# Keyboard_Mouse_LED_Monitor.net
KiCad netlist of a schematic drawn in Altium Designer
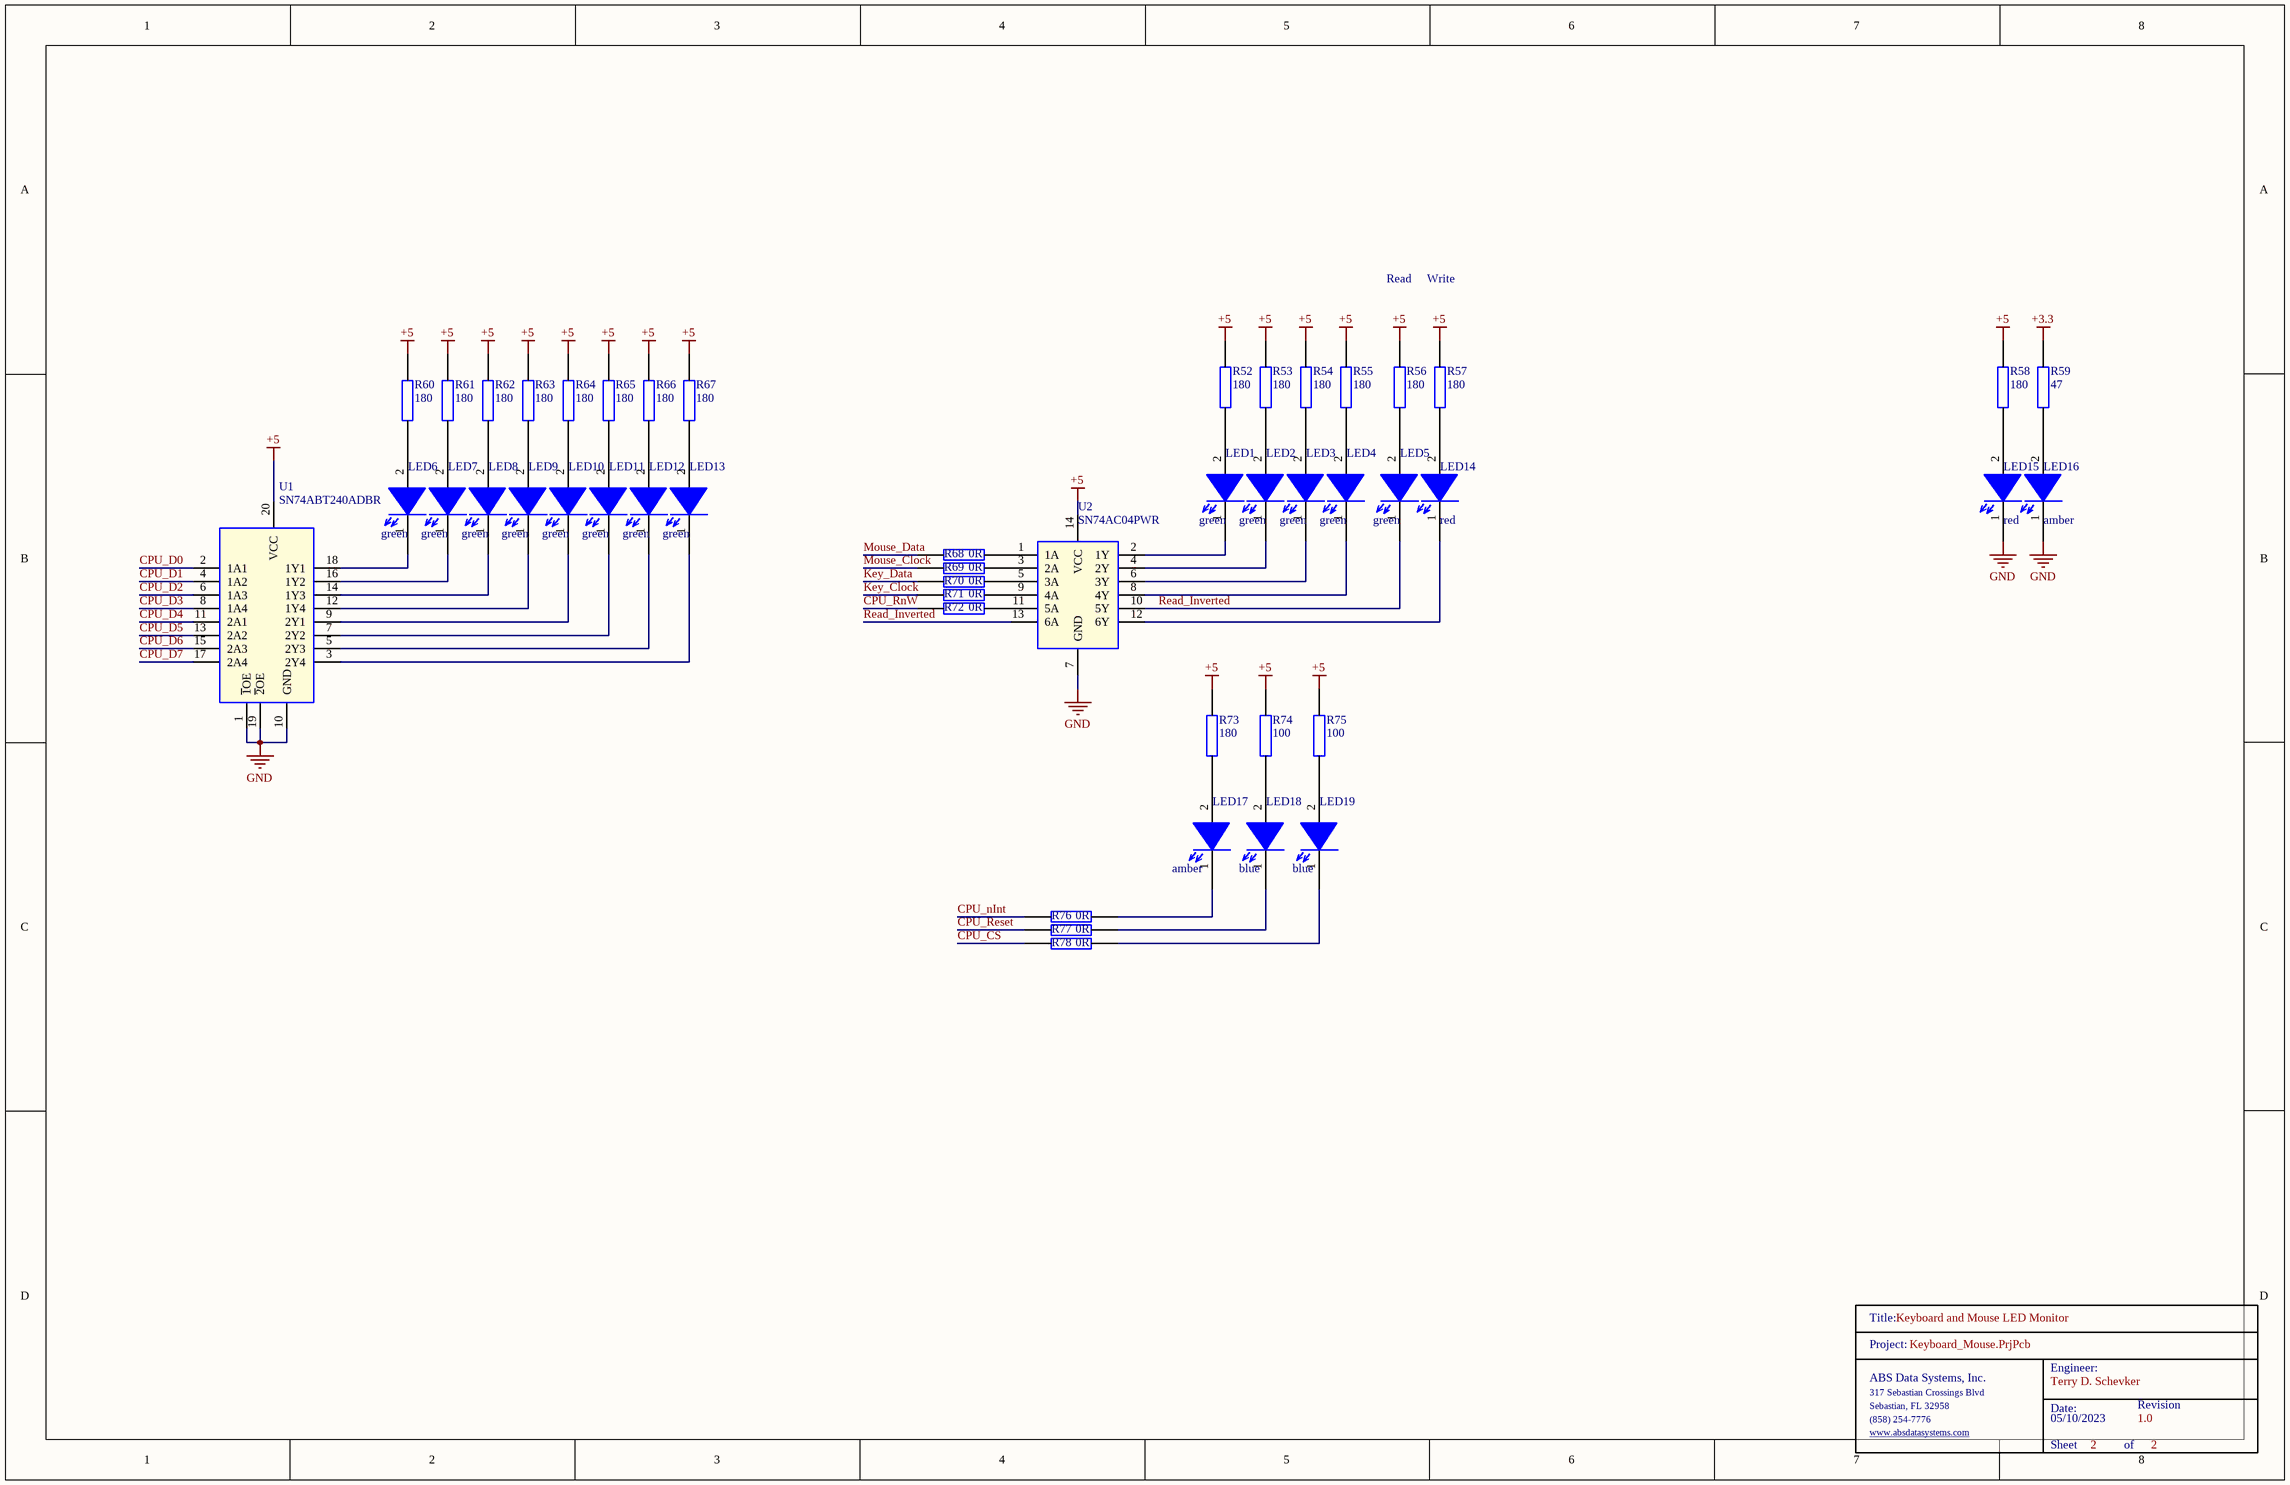
[diagram p0: Keyboard_Mouse_LED_Monitor.SchDoc]

(export (version "E")
  (design (tool "Eeschema 10.0.6"))
  (components
    (comp (ref "LED1")
      (value "green")
      (footprint "0603_Diode")
      (description "Wurth Elektronik 0603 green")
      (fields
        (field (name "MANUFACTURER") "Wurth Electronics")
        (field (name "MANUFACTURER PART NUMBER") "150060GS75000")
      )
      (libsource (lib "Misc") (part "150060GS75000"))
    )
    (comp (ref "LED2")
      (value "green")
      (footprint "0603_Diode")
      (description "Wurth Elektronik 0603 green")
      (fields
        (field (name "MANUFACTURER") "Wurth Electronics")
        (field (name "MANUFACTURER PART NUMBER") "150060GS75000")
      )
      (libsource (lib "Misc") (part "150060GS75000"))
    )
    (comp (ref "LED3")
      (value "green")
      (footprint "0603_Diode")
      (description "Wurth Elektronik 0603 green")
      (fields
        (field (name "MANUFACTURER") "Wurth Electronics")
        (field (name "MANUFACTURER PART NUMBER") "150060GS75000")
      )
      (libsource (lib "Misc") (part "150060GS75000"))
    )
    (comp (ref "LED4")
      (value "green")
      (footprint "0603_Diode")
      (description "Wurth Elektronik 0603 green")
      (fields
        (field (name "MANUFACTURER") "Wurth Electronics")
        (field (name "MANUFACTURER PART NUMBER") "150060GS75000")
      )
      (libsource (lib "Misc") (part "150060GS75000"))
    )
    (comp (ref "LED5")
      (value "green")
      (footprint "0603_Diode")
      (description "Wurth Elektronik 0603 green")
      (fields
        (field (name "MANUFACTURER") "Wurth Electronics")
        (field (name "MANUFACTURER PART NUMBER") "150060GS75000")
      )
      (libsource (lib "Misc") (part "150060GS75000"))
    )
    (comp (ref "LED6")
      (value "green")
      (footprint "0603_Diode")
      (description "Wurth Elektronik 0603 green")
      (fields
        (field (name "MANUFACTURER") "Wurth Electronics")
        (field (name "MANUFACTURER PART NUMBER") "150060GS75000")
      )
      (libsource (lib "Misc") (part "150060GS75000"))
    )
    (comp (ref "LED7")
      (value "green")
      (footprint "0603_Diode")
      (description "Wurth Elektronik 0603 green")
      (fields
        (field (name "MANUFACTURER") "Wurth Electronics")
        (field (name "MANUFACTURER PART NUMBER") "150060GS75000")
      )
      (libsource (lib "Misc") (part "150060GS75000"))
    )
    (comp (ref "LED8")
      (value "green")
      (footprint "0603_Diode")
      (description "Wurth Elektronik 0603 green")
      (fields
        (field (name "MANUFACTURER") "Wurth Electronics")
        (field (name "MANUFACTURER PART NUMBER") "150060GS75000")
      )
      (libsource (lib "Misc") (part "150060GS75000"))
    )
    (comp (ref "LED9")
      (value "green")
      (footprint "0603_Diode")
      (description "Wurth Elektronik 0603 green")
      (fields
        (field (name "MANUFACTURER") "Wurth Electronics")
        (field (name "MANUFACTURER PART NUMBER") "150060GS75000")
      )
      (libsource (lib "Misc") (part "150060GS75000"))
    )
    (comp (ref "LED10")
      (value "green")
      (footprint "0603_Diode")
      (description "Wurth Elektronik 0603 green")
      (fields
        (field (name "MANUFACTURER") "Wurth Electronics")
        (field (name "MANUFACTURER PART NUMBER") "150060GS75000")
      )
      (libsource (lib "Misc") (part "150060GS75000"))
    )
    (comp (ref "LED11")
      (value "green")
      (footprint "0603_Diode")
      (description "Wurth Elektronik 0603 green")
      (fields
        (field (name "MANUFACTURER") "Wurth Electronics")
        (field (name "MANUFACTURER PART NUMBER") "150060GS75000")
      )
      (libsource (lib "Misc") (part "150060GS75000"))
    )
    (comp (ref "LED12")
      (value "green")
      (footprint "0603_Diode")
      (description "Wurth Elektronik 0603 green")
      (fields
        (field (name "MANUFACTURER") "Wurth Electronics")
        (field (name "MANUFACTURER PART NUMBER") "150060GS75000")
      )
      (libsource (lib "Misc") (part "150060GS75000"))
    )
    (comp (ref "LED13")
      (value "green")
      (footprint "0603_Diode")
      (description "Wurth Elektronik 0603 green")
      (fields
        (field (name "MANUFACTURER") "Wurth Electronics")
        (field (name "MANUFACTURER PART NUMBER") "150060GS75000")
      )
      (libsource (lib "Misc") (part "150060GS75000"))
    )
    (comp (ref "LED14")
      (value "red")
      (footprint "0603_Diode")
      (description "Wurth Elektronik 0603 red")
      (fields
        (field (name "MANUFACTURER") "Wurth Electronics")
        (field (name "MANUFACTURER PART NUMBER") "150060GS75000")
      )
      (libsource (lib "Misc") (part "150060RS75000"))
    )
    (comp (ref "LED15")
      (value "red")
      (footprint "0603_Diode")
      (description "Wurth Elektronik 0603 red")
      (fields
        (field (name "MANUFACTURER") "Wurth Electronics")
        (field (name "MANUFACTURER PART NUMBER") "150060GS75000")
      )
      (libsource (lib "Misc") (part "150060RS75000"))
    )
    (comp (ref "LED16")
      (value "amber")
      (footprint "0603_Diode")
      (description "Wurth Elektronik 0603 amber")
      (fields
        (field (name "MANUFACTURER") "Wurth Electronics")
        (field (name "MANUFACTURER PART NUMBER") "150060GS75000")
      )
      (libsource (lib "Misc") (part "150060AS75000"))
    )
    (comp (ref "LED17")
      (value "amber")
      (footprint "0603_Diode")
      (description "Wurth Elektronik 0603 amber")
      (fields
        (field (name "MANUFACTURER") "Wurth Electronics")
        (field (name "MANUFACTURER PART NUMBER") "150060GS75000")
      )
      (libsource (lib "Misc") (part "150060AS75000"))
    )
    (comp (ref "LED18")
      (value "blue")
      (footprint "0603_Diode")
      (description "Wurth Elektronik 0603 blue")
      (fields
        (field (name "MANUFACTURER") "Wurth Electronics")
        (field (name "MANUFACTURER PART NUMBER") "150060GS75000")
      )
      (libsource (lib "Misc") (part "150060BS75000"))
    )
    (comp (ref "LED19")
      (value "blue")
      (footprint "0603_Diode")
      (description "Wurth Elektronik 0603 blue")
      (fields
        (field (name "MANUFACTURER") "Wurth Electronics")
        (field (name "MANUFACTURER PART NUMBER") "150060GS75000")
      )
      (libsource (lib "Misc") (part "150060BS75000"))
    )
    (comp (ref "R52")
      (value "180")
      (footprint "0603")
      (description "YAGEO 0603 180 ohm")
      (fields
        (field (name "MOUSER PART NUMBER") "603-RC0603JR-070RL")
        (field (name "MANUFACTURER_PART_NUMBER") "RC0603JR-070RL")
      )
      (libsource (lib "Resistors") (part "RC0603FR-13180RL"))
    )
    (comp (ref "R53")
      (value "180")
      (footprint "0603")
      (description "YAGEO 0603 180 ohm")
      (fields
        (field (name "MOUSER PART NUMBER") "603-RC0603JR-070RL")
        (field (name "MANUFACTURER_PART_NUMBER") "RC0603JR-070RL")
      )
      (libsource (lib "Resistors") (part "RC0603FR-13180RL"))
    )
    (comp (ref "R54")
      (value "180")
      (footprint "0603")
      (description "YAGEO 0603 180 ohm")
      (fields
        (field (name "MOUSER PART NUMBER") "603-RC0603JR-070RL")
        (field (name "MANUFACTURER_PART_NUMBER") "RC0603JR-070RL")
      )
      (libsource (lib "Resistors") (part "RC0603FR-13180RL"))
    )
    (comp (ref "R55")
      (value "180")
      (footprint "0603")
      (description "YAGEO 0603 180 ohm")
      (fields
        (field (name "MOUSER PART NUMBER") "603-RC0603JR-070RL")
        (field (name "MANUFACTURER_PART_NUMBER") "RC0603JR-070RL")
      )
      (libsource (lib "Resistors") (part "RC0603FR-13180RL"))
    )
    (comp (ref "R56")
      (value "180")
      (footprint "0603")
      (description "YAGEO 0603 180 ohm")
      (fields
        (field (name "MOUSER PART NUMBER") "603-RC0603JR-070RL")
        (field (name "MANUFACTURER_PART_NUMBER") "RC0603JR-070RL")
      )
      (libsource (lib "Resistors") (part "RC0603FR-13180RL"))
    )
    (comp (ref "R57")
      (value "180")
      (footprint "0603")
      (description "YAGEO 0603 180 ohm")
      (fields
        (field (name "MOUSER PART NUMBER") "603-RC0603JR-070RL")
        (field (name "MANUFACTURER_PART_NUMBER") "RC0603JR-070RL")
      )
      (libsource (lib "Resistors") (part "RC0603FR-13180RL"))
    )
    (comp (ref "R58")
      (value "180")
      (footprint "0603")
      (description "YAGEO 0603 180 ohm")
      (fields
        (field (name "MOUSER PART NUMBER") "603-RC0603JR-070RL")
        (field (name "MANUFACTURER_PART_NUMBER") "RC0603JR-070RL")
      )
      (libsource (lib "Resistors") (part "RC0603FR-13180RL"))
    )
    (comp (ref "R59")
      (value "47")
      (footprint "0603")
      (description "YAGEO 0603 47")
      (fields
        (field (name "MOUSER PART NUMBER") "603-RC0603JR-070RL")
        (field (name "MANUFACTURER_PART_NUMBER") "RC0603JR-070RL")
      )
      (libsource (lib "Resistors") (part "RC0603FR-0747KL"))
    )
    (comp (ref "R60")
      (value "180")
      (footprint "0603")
      (description "YAGEO 0603 180 ohm")
      (fields
        (field (name "MOUSER PART NUMBER") "603-RC0603JR-070RL")
        (field (name "MANUFACTURER_PART_NUMBER") "RC0603JR-070RL")
      )
      (libsource (lib "Resistors") (part "RC0603FR-13180RL"))
    )
    (comp (ref "R61")
      (value "180")
      (footprint "0603")
      (description "YAGEO 0603 180 ohm")
      (fields
        (field (name "MOUSER PART NUMBER") "603-RC0603JR-070RL")
        (field (name "MANUFACTURER_PART_NUMBER") "RC0603JR-070RL")
      )
      (libsource (lib "Resistors") (part "RC0603FR-13180RL"))
    )
    (comp (ref "R62")
      (value "180")
      (footprint "0603")
      (description "YAGEO 0603 180 ohm")
      (fields
        (field (name "MOUSER PART NUMBER") "603-RC0603JR-070RL")
        (field (name "MANUFACTURER_PART_NUMBER") "RC0603JR-070RL")
      )
      (libsource (lib "Resistors") (part "RC0603FR-13180RL"))
    )
    (comp (ref "R63")
      (value "180")
      (footprint "0603")
      (description "YAGEO 0603 180 ohm")
      (fields
        (field (name "MOUSER PART NUMBER") "603-RC0603JR-070RL")
        (field (name "MANUFACTURER_PART_NUMBER") "RC0603JR-070RL")
      )
      (libsource (lib "Resistors") (part "RC0603FR-13180RL"))
    )
    (comp (ref "R64")
      (value "180")
      (footprint "0603")
      (description "YAGEO 0603 180 ohm")
      (fields
        (field (name "MOUSER PART NUMBER") "603-RC0603JR-070RL")
        (field (name "MANUFACTURER_PART_NUMBER") "RC0603JR-070RL")
      )
      (libsource (lib "Resistors") (part "RC0603FR-13180RL"))
    )
    (comp (ref "R65")
      (value "180")
      (footprint "0603")
      (description "YAGEO 0603 180 ohm")
      (fields
        (field (name "MOUSER PART NUMBER") "603-RC0603JR-070RL")
        (field (name "MANUFACTURER_PART_NUMBER") "RC0603JR-070RL")
      )
      (libsource (lib "Resistors") (part "RC0603FR-13180RL"))
    )
    (comp (ref "R66")
      (value "180")
      (footprint "0603")
      (description "YAGEO 0603 180 ohm")
      (fields
        (field (name "MOUSER PART NUMBER") "603-RC0603JR-070RL")
        (field (name "MANUFACTURER_PART_NUMBER") "RC0603JR-070RL")
      )
      (libsource (lib "Resistors") (part "RC0603FR-13180RL"))
    )
    (comp (ref "R67")
      (value "180")
      (footprint "0603")
      (description "YAGEO 0603 180 ohm")
      (fields
        (field (name "MOUSER PART NUMBER") "603-RC0603JR-070RL")
        (field (name "MANUFACTURER_PART_NUMBER") "RC0603JR-070RL")
      )
      (libsource (lib "Resistors") (part "RC0603FR-13180RL"))
    )
    (comp (ref "R68")
      (value "0R")
      (footprint "0603")
      (description "YAGEO 0603 0 ohm")
      (fields
        (field (name "MOUSER PART NUMBER") "603-RC0603JR-070RL")
        (field (name "MANUFACTURER_PART_NUMBER") "RC0603JR-070RL")
      )
      (libsource (lib "Resistors") (part "RC0603JR-070RL"))
    )
    (comp (ref "R69")
      (value "0R")
      (footprint "0603")
      (description "YAGEO 0603 0 ohm")
      (fields
        (field (name "MOUSER PART NUMBER") "603-RC0603JR-070RL")
        (field (name "MANUFACTURER_PART_NUMBER") "RC0603JR-070RL")
      )
      (libsource (lib "Resistors") (part "RC0603JR-070RL"))
    )
    (comp (ref "R70")
      (value "0R")
      (footprint "0603")
      (description "YAGEO 0603 0 ohm")
      (fields
        (field (name "MOUSER PART NUMBER") "603-RC0603JR-070RL")
        (field (name "MANUFACTURER_PART_NUMBER") "RC0603JR-070RL")
      )
      (libsource (lib "Resistors") (part "RC0603JR-070RL"))
    )
    (comp (ref "R71")
      (value "0R")
      (footprint "0603")
      (description "YAGEO 0603 0 ohm")
      (fields
        (field (name "MOUSER PART NUMBER") "603-RC0603JR-070RL")
        (field (name "MANUFACTURER_PART_NUMBER") "RC0603JR-070RL")
      )
      (libsource (lib "Resistors") (part "RC0603JR-070RL"))
    )
    (comp (ref "R72")
      (value "0R")
      (footprint "0603")
      (description "YAGEO 0603 0 ohm")
      (fields
        (field (name "MOUSER PART NUMBER") "603-RC0603JR-070RL")
        (field (name "MANUFACTURER_PART_NUMBER") "RC0603JR-070RL")
      )
      (libsource (lib "Resistors") (part "RC0603JR-070RL"))
    )
    (comp (ref "R73")
      (value "180")
      (footprint "0603")
      (description "YAGEO 0603 180 ohm")
      (fields
        (field (name "MOUSER PART NUMBER") "603-RC0603JR-070RL")
        (field (name "MANUFACTURER_PART_NUMBER") "RC0603JR-070RL")
      )
      (libsource (lib "Resistors") (part "RC0603FR-13180RL"))
    )
    (comp (ref "R74")
      (value "100")
      (footprint "0603")
      (description "YAGEO 0603 100 ohm")
      (fields
        (field (name "MOUSER PART NUMBER") "603-RC0603JR-070RL")
        (field (name "MANUFACTURER_PART_NUMBER") "RC0603JR-070RL")
      )
      (libsource (lib "Resistors") (part "RC0603FR-10100RL"))
    )
    (comp (ref "R75")
      (value "100")
      (footprint "0603")
      (description "YAGEO 0603 100 ohm")
      (fields
        (field (name "MOUSER PART NUMBER") "603-RC0603JR-070RL")
        (field (name "MANUFACTURER_PART_NUMBER") "RC0603JR-070RL")
      )
      (libsource (lib "Resistors") (part "RC0603FR-10100RL"))
    )
    (comp (ref "R76")
      (value "0R")
      (footprint "0603")
      (description "YAGEO 0603 0 ohm")
      (fields
        (field (name "MOUSER PART NUMBER") "603-RC0603JR-070RL")
        (field (name "MANUFACTURER_PART_NUMBER") "RC0603JR-070RL")
      )
      (libsource (lib "Resistors") (part "RC0603JR-070RL"))
    )
    (comp (ref "R77")
      (value "0R")
      (footprint "0603")
      (description "YAGEO 0603 0 ohm")
      (fields
        (field (name "MOUSER PART NUMBER") "603-RC0603JR-070RL")
        (field (name "MANUFACTURER_PART_NUMBER") "RC0603JR-070RL")
      )
      (libsource (lib "Resistors") (part "RC0603JR-070RL"))
    )
    (comp (ref "R78")
      (value "0R")
      (footprint "0603")
      (description "YAGEO 0603 0 ohm")
      (fields
        (field (name "MOUSER PART NUMBER") "603-RC0603JR-070RL")
        (field (name "MANUFACTURER_PART_NUMBER") "RC0603JR-070RL")
      )
      (libsource (lib "Resistors") (part "RC0603JR-070RL"))
    )
    (comp (ref "TitleBlock_2") (value "TitleBlock") (libsource (lib "Misc") (part "TitleBlock")))
    (comp (ref "U1")
      (value "SN74ABT240ADBR")
      (footprint "SOP65P780X200-20N")
      (description "Octal Buffers/Drivers With 3-State Outputs")
      (fields (field (name "MOUSER PART NUMBER") "595-SN74ABT240ADBR"))
      (libsource (lib "Logic") (part "SN74ABT240ADBR"))
    )
    (comp (ref "U2")
      (value "SN74AC04PWR")
      (footprint "SOP65P640X120-14N")
      (description "Hex Inverters")
      (fields (field (name "MOUSER PART NUMBER") "595-SN74AC04PWR"))
      (libsource (lib "Logic") (part "SN74AC04PWR"))
    )
  )
  (nets
    (net (code "1") (name "+3.3") (class "Default")
      (node (ref "R59") (pin "1") (pinfunction "1_1") (pintype "passive"))
    )
    (net (code "2") (name "+5") (class "Default")
      (node (ref "R52") (pin "2") (pinfunction "2_2") (pintype "passive"))
      (node (ref "R53") (pin "2") (pinfunction "2_2") (pintype "passive"))
      (node (ref "R54") (pin "2") (pinfunction "2_2") (pintype "passive"))
      (node (ref "R55") (pin "2") (pinfunction "2_2") (pintype "passive"))
      (node (ref "R56") (pin "2") (pinfunction "2_2") (pintype "passive"))
      (node (ref "R57") (pin "2") (pinfunction "2_2") (pintype "passive"))
      (node (ref "R58") (pin "2") (pinfunction "2_2") (pintype "passive"))
      (node (ref "R60") (pin "2") (pinfunction "2_2") (pintype "passive"))
      (node (ref "R61") (pin "2") (pinfunction "2_2") (pintype "passive"))
      (node (ref "R62") (pin "2") (pinfunction "2_2") (pintype "passive"))
      (node (ref "R63") (pin "2") (pinfunction "2_2") (pintype "passive"))
      (node (ref "R64") (pin "2") (pinfunction "2_2") (pintype "passive"))
      (node (ref "R65") (pin "2") (pinfunction "2_2") (pintype "passive"))
      (node (ref "R66") (pin "2") (pinfunction "2_2") (pintype "passive"))
      (node (ref "R67") (pin "2") (pinfunction "2_2") (pintype "passive"))
      (node (ref "R73") (pin "2") (pinfunction "2_2") (pintype "passive"))
      (node (ref "R74") (pin "1") (pinfunction "1_1") (pintype "passive"))
      (node (ref "R75") (pin "1") (pinfunction "1_1") (pintype "passive"))
      (node (ref "U1") (pin "20") (pinfunction "VCC_20") (pintype "passive"))
      (node (ref "U2") (pin "14") (pinfunction "VCC_14") (pintype "passive"))
    )
    (net (code "3") (name "/CPU_CS") (class "Default")
      (node (ref "R78") (pin "1") (pinfunction "1_1") (pintype "passive"))
    )
    (net (code "4") (name "/CPU_D0") (class "Default")
      (node (ref "U1") (pin "2") (pinfunction "1A1_2") (pintype "passive"))
    )
    (net (code "5") (name "/CPU_D1") (class "Default")
      (node (ref "U1") (pin "4") (pinfunction "1A2_4") (pintype "passive"))
    )
    (net (code "6") (name "/CPU_D2") (class "Default")
      (node (ref "U1") (pin "6") (pinfunction "1A3_6") (pintype "passive"))
    )
    (net (code "7") (name "/CPU_D3") (class "Default")
      (node (ref "U1") (pin "8") (pinfunction "1A4_8") (pintype "passive"))
    )
    (net (code "8") (name "/CPU_D4") (class "Default")
      (node (ref "U1") (pin "11") (pinfunction "2A1_11") (pintype "passive"))
    )
    (net (code "9") (name "/CPU_D5") (class "Default")
      (node (ref "U1") (pin "13") (pinfunction "2A2_13") (pintype "passive"))
    )
    (net (code "10") (name "/CPU_D6") (class "Default")
      (node (ref "U1") (pin "15") (pinfunction "2A3_15") (pintype "passive"))
    )
    (net (code "11") (name "/CPU_D7") (class "Default")
      (node (ref "U1") (pin "17") (pinfunction "2A4_17") (pintype "passive"))
    )
    (net (code "12") (name "/CPU_Reset") (class "Default")
      (node (ref "R77") (pin "1") (pinfunction "1_1") (pintype "passive"))
    )
    (net (code "13") (name "/CPU_RnW") (class "Default")
      (node (ref "R72") (pin "1") (pinfunction "1_1") (pintype "passive"))
    )
    (net (code "14") (name "/CPU_nInt") (class "Default")
      (node (ref "R76") (pin "1") (pinfunction "1_1") (pintype "passive"))
    )
    (net (code "15") (name "/Key_Clock") (class "Default")
      (node (ref "R71") (pin "1") (pinfunction "1_1") (pintype "passive"))
    )
    (net (code "16") (name "/Key_Data") (class "Default")
      (node (ref "R70") (pin "1") (pinfunction "1_1") (pintype "passive"))
    )
    (net (code "17") (name "/Mouse_Clock") (class "Default")
      (node (ref "R69") (pin "1") (pinfunction "1_1") (pintype "passive"))
    )
    (net (code "18") (name "/Mouse_Data") (class "Default")
      (node (ref "R68") (pin "1") (pinfunction "1_1") (pintype "passive"))
    )
    (net (code "19") (name "/Read_Inverted") (class "Default")
      (node (ref "LED5") (pin "1") (pinfunction "K_1") (pintype "passive"))
      (node (ref "U2") (pin "10") (pinfunction "5Y_10") (pintype "passive"))
      (node (ref "U2") (pin "13") (pinfunction "6A_13") (pintype "passive"))
    )
    (net (code "20") (name "GND") (class "Default")
      (node (ref "LED15") (pin "1") (pinfunction "K_1") (pintype "passive"))
      (node (ref "LED16") (pin "1") (pinfunction "K_1") (pintype "passive"))
      (node (ref "U1") (pin "1") (pinfunction "~{1}OE_1") (pintype "passive"))
      (node (ref "U1") (pin "10") (pinfunction "GND_10") (pintype "passive"))
      (node (ref "U1") (pin "19") (pinfunction "~{2}OE_19") (pintype "passive"))
      (node (ref "U2") (pin "7") (pinfunction "GND_7") (pintype "passive"))
    )
    (net (code "21") (name "Net-(LED1-A)") (class "Default")
      (node (ref "LED1") (pin "2") (pinfunction "A_2") (pintype "passive"))
      (node (ref "R52") (pin "1") (pinfunction "1_1") (pintype "passive"))
    )
    (net (code "22") (name "Net-(LED1-K)") (class "Default")
      (node (ref "LED1") (pin "1") (pinfunction "K_1") (pintype "passive"))
      (node (ref "U2") (pin "2") (pinfunction "1Y_2") (pintype "passive"))
    )
    (net (code "23") (name "Net-(LED2-A)") (class "Default")
      (node (ref "LED2") (pin "2") (pinfunction "A_2") (pintype "passive"))
      (node (ref "R53") (pin "1") (pinfunction "1_1") (pintype "passive"))
    )
    (net (code "24") (name "Net-(LED2-K)") (class "Default")
      (node (ref "LED2") (pin "1") (pinfunction "K_1") (pintype "passive"))
      (node (ref "U2") (pin "4") (pinfunction "2Y_4") (pintype "passive"))
    )
    (net (code "25") (name "Net-(LED3-A)") (class "Default")
      (node (ref "LED3") (pin "2") (pinfunction "A_2") (pintype "passive"))
      (node (ref "R54") (pin "1") (pinfunction "1_1") (pintype "passive"))
    )
    (net (code "26") (name "Net-(LED3-K)") (class "Default")
      (node (ref "LED3") (pin "1") (pinfunction "K_1") (pintype "passive"))
      (node (ref "U2") (pin "6") (pinfunction "3Y_6") (pintype "passive"))
    )
    (net (code "27") (name "Net-(LED4-A)") (class "Default")
      (node (ref "LED4") (pin "2") (pinfunction "A_2") (pintype "passive"))
      (node (ref "R55") (pin "1") (pinfunction "1_1") (pintype "passive"))
    )
    (net (code "28") (name "Net-(LED4-K)") (class "Default")
      (node (ref "LED4") (pin "1") (pinfunction "K_1") (pintype "passive"))
      (node (ref "U2") (pin "8") (pinfunction "4Y_8") (pintype "passive"))
    )
    (net (code "29") (name "Net-(LED5-A)") (class "Default")
      (node (ref "LED5") (pin "2") (pinfunction "A_2") (pintype "passive"))
      (node (ref "R56") (pin "1") (pinfunction "1_1") (pintype "passive"))
    )
    (net (code "30") (name "Net-(LED6-A)") (class "Default")
      (node (ref "LED6") (pin "2") (pinfunction "A_2") (pintype "passive"))
      (node (ref "R60") (pin "1") (pinfunction "1_1") (pintype "passive"))
    )
    (net (code "31") (name "Net-(LED6-K)") (class "Default")
      (node (ref "LED6") (pin "1") (pinfunction "K_1") (pintype "passive"))
      (node (ref "U1") (pin "18") (pinfunction "1Y1_18") (pintype "passive"))
    )
    (net (code "32") (name "Net-(LED7-A)") (class "Default")
      (node (ref "LED7") (pin "2") (pinfunction "A_2") (pintype "passive"))
      (node (ref "R61") (pin "1") (pinfunction "1_1") (pintype "passive"))
    )
    (net (code "33") (name "Net-(LED7-K)") (class "Default")
      (node (ref "LED7") (pin "1") (pinfunction "K_1") (pintype "passive"))
      (node (ref "U1") (pin "16") (pinfunction "1Y2_16") (pintype "passive"))
    )
    (net (code "34") (name "Net-(LED8-A)") (class "Default")
      (node (ref "LED8") (pin "2") (pinfunction "A_2") (pintype "passive"))
      (node (ref "R62") (pin "1") (pinfunction "1_1") (pintype "passive"))
    )
    (net (code "35") (name "Net-(LED8-K)") (class "Default")
      (node (ref "LED8") (pin "1") (pinfunction "K_1") (pintype "passive"))
      (node (ref "U1") (pin "14") (pinfunction "1Y3_14") (pintype "passive"))
    )
    (net (code "36") (name "Net-(LED9-A)") (class "Default")
      (node (ref "LED9") (pin "2") (pinfunction "A_2") (pintype "passive"))
      (node (ref "R63") (pin "1") (pinfunction "1_1") (pintype "passive"))
    )
    (net (code "37") (name "Net-(LED9-K)") (class "Default")
      (node (ref "LED9") (pin "1") (pinfunction "K_1") (pintype "passive"))
      (node (ref "U1") (pin "12") (pinfunction "1Y4_12") (pintype "passive"))
    )
    (net (code "38") (name "Net-(LED10-A)") (class "Default")
      (node (ref "LED10") (pin "2") (pinfunction "A_2") (pintype "passive"))
      (node (ref "R64") (pin "1") (pinfunction "1_1") (pintype "passive"))
    )
    (net (code "39") (name "Net-(LED10-K)") (class "Default")
      (node (ref "LED10") (pin "1") (pinfunction "K_1") (pintype "passive"))
      (node (ref "U1") (pin "9") (pinfunction "2Y1_9") (pintype "passive"))
    )
    (net (code "40") (name "Net-(LED11-A)") (class "Default")
      (node (ref "LED11") (pin "2") (pinfunction "A_2") (pintype "passive"))
      (node (ref "R65") (pin "1") (pinfunction "1_1") (pintype "passive"))
    )
    (net (code "41") (name "Net-(LED11-K)") (class "Default")
      (node (ref "LED11") (pin "1") (pinfunction "K_1") (pintype "passive"))
      (node (ref "U1") (pin "7") (pinfunction "2Y2_7") (pintype "passive"))
    )
    (net (code "42") (name "Net-(LED12-A)") (class "Default")
      (node (ref "LED12") (pin "2") (pinfunction "A_2") (pintype "passive"))
      (node (ref "R66") (pin "1") (pinfunction "1_1") (pintype "passive"))
    )
    (net (code "43") (name "Net-(LED12-K)") (class "Default")
      (node (ref "LED12") (pin "1") (pinfunction "K_1") (pintype "passive"))
      (node (ref "U1") (pin "5") (pinfunction "2Y3_5") (pintype "passive"))
    )
    (net (code "44") (name "Net-(LED13-A)") (class "Default")
      (node (ref "LED13") (pin "2") (pinfunction "A_2") (pintype "passive"))
      (node (ref "R67") (pin "1") (pinfunction "1_1") (pintype "passive"))
    )
    (net (code "45") (name "Net-(LED13-K)") (class "Default")
      (node (ref "LED13") (pin "1") (pinfunction "K_1") (pintype "passive"))
      (node (ref "U1") (pin "3") (pinfunction "2Y4_3") (pintype "passive"))
    )
    (net (code "46") (name "Net-(LED14-A)") (class "Default")
      (node (ref "LED14") (pin "2") (pinfunction "A_2") (pintype "passive"))
      (node (ref "R57") (pin "1") (pinfunction "1_1") (pintype "passive"))
    )
    (net (code "47") (name "Net-(LED14-K)") (class "Default")
      (node (ref "LED14") (pin "1") (pinfunction "K_1") (pintype "passive"))
      (node (ref "U2") (pin "12") (pinfunction "6Y_12") (pintype "passive"))
    )
    (net (code "48") (name "Net-(LED15-A)") (class "Default")
      (node (ref "LED15") (pin "2") (pinfunction "A_2") (pintype "passive"))
      (node (ref "R58") (pin "1") (pinfunction "1_1") (pintype "passive"))
    )
    (net (code "49") (name "Net-(LED16-A)") (class "Default")
      (node (ref "LED16") (pin "2") (pinfunction "A_2") (pintype "passive"))
      (node (ref "R59") (pin "2") (pinfunction "2_2") (pintype "passive"))
    )
    (net (code "50") (name "Net-(LED17-A)") (class "Default")
      (node (ref "LED17") (pin "2") (pinfunction "A_2") (pintype "passive"))
      (node (ref "R73") (pin "1") (pinfunction "1_1") (pintype "passive"))
    )
    (net (code "51") (name "Net-(LED17-K)") (class "Default")
      (node (ref "LED17") (pin "1") (pinfunction "K_1") (pintype "passive"))
      (node (ref "R76") (pin "2") (pinfunction "2_2") (pintype "passive"))
    )
    (net (code "52") (name "Net-(LED18-A)") (class "Default")
      (node (ref "LED18") (pin "2") (pinfunction "A_2") (pintype "passive"))
      (node (ref "R74") (pin "2") (pinfunction "2_2") (pintype "passive"))
    )
    (net (code "53") (name "Net-(LED18-K)") (class "Default")
      (node (ref "LED18") (pin "1") (pinfunction "K_1") (pintype "passive"))
      (node (ref "R77") (pin "2") (pinfunction "2_2") (pintype "passive"))
    )
    (net (code "54") (name "Net-(LED19-A)") (class "Default")
      (node (ref "LED19") (pin "2") (pinfunction "A_2") (pintype "passive"))
      (node (ref "R75") (pin "2") (pinfunction "2_2") (pintype "passive"))
    )
    (net (code "55") (name "Net-(LED19-K)") (class "Default")
      (node (ref "LED19") (pin "1") (pinfunction "K_1") (pintype "passive"))
      (node (ref "R78") (pin "2") (pinfunction "2_2") (pintype "passive"))
    )
    (net (code "56") (name "Net-(U2-1A)") (class "Default")
      (node (ref "R68") (pin "2") (pinfunction "2_2") (pintype "passive"))
      (node (ref "U2") (pin "1") (pinfunction "1A_1") (pintype "passive"))
    )
    (net (code "57") (name "Net-(U2-2A)") (class "Default")
      (node (ref "R69") (pin "2") (pinfunction "2_2") (pintype "passive"))
      (node (ref "U2") (pin "3") (pinfunction "2A_3") (pintype "passive"))
    )
    (net (code "58") (name "Net-(U2-3A)") (class "Default")
      (node (ref "R70") (pin "2") (pinfunction "2_2") (pintype "passive"))
      (node (ref "U2") (pin "5") (pinfunction "3A_5") (pintype "passive"))
    )
    (net (code "59") (name "Net-(U2-4A)") (class "Default")
      (node (ref "R71") (pin "2") (pinfunction "2_2") (pintype "passive"))
      (node (ref "U2") (pin "9") (pinfunction "4A_9") (pintype "passive"))
    )
    (net (code "60") (name "Net-(U2-5A)") (class "Default")
      (node (ref "R72") (pin "2") (pinfunction "2_2") (pintype "passive"))
      (node (ref "U2") (pin "11") (pinfunction "5A_11") (pintype "passive"))
    )
  )
)
